# SPI_IO.net
KiCad netlist of a schematic drawn in Altium Designer
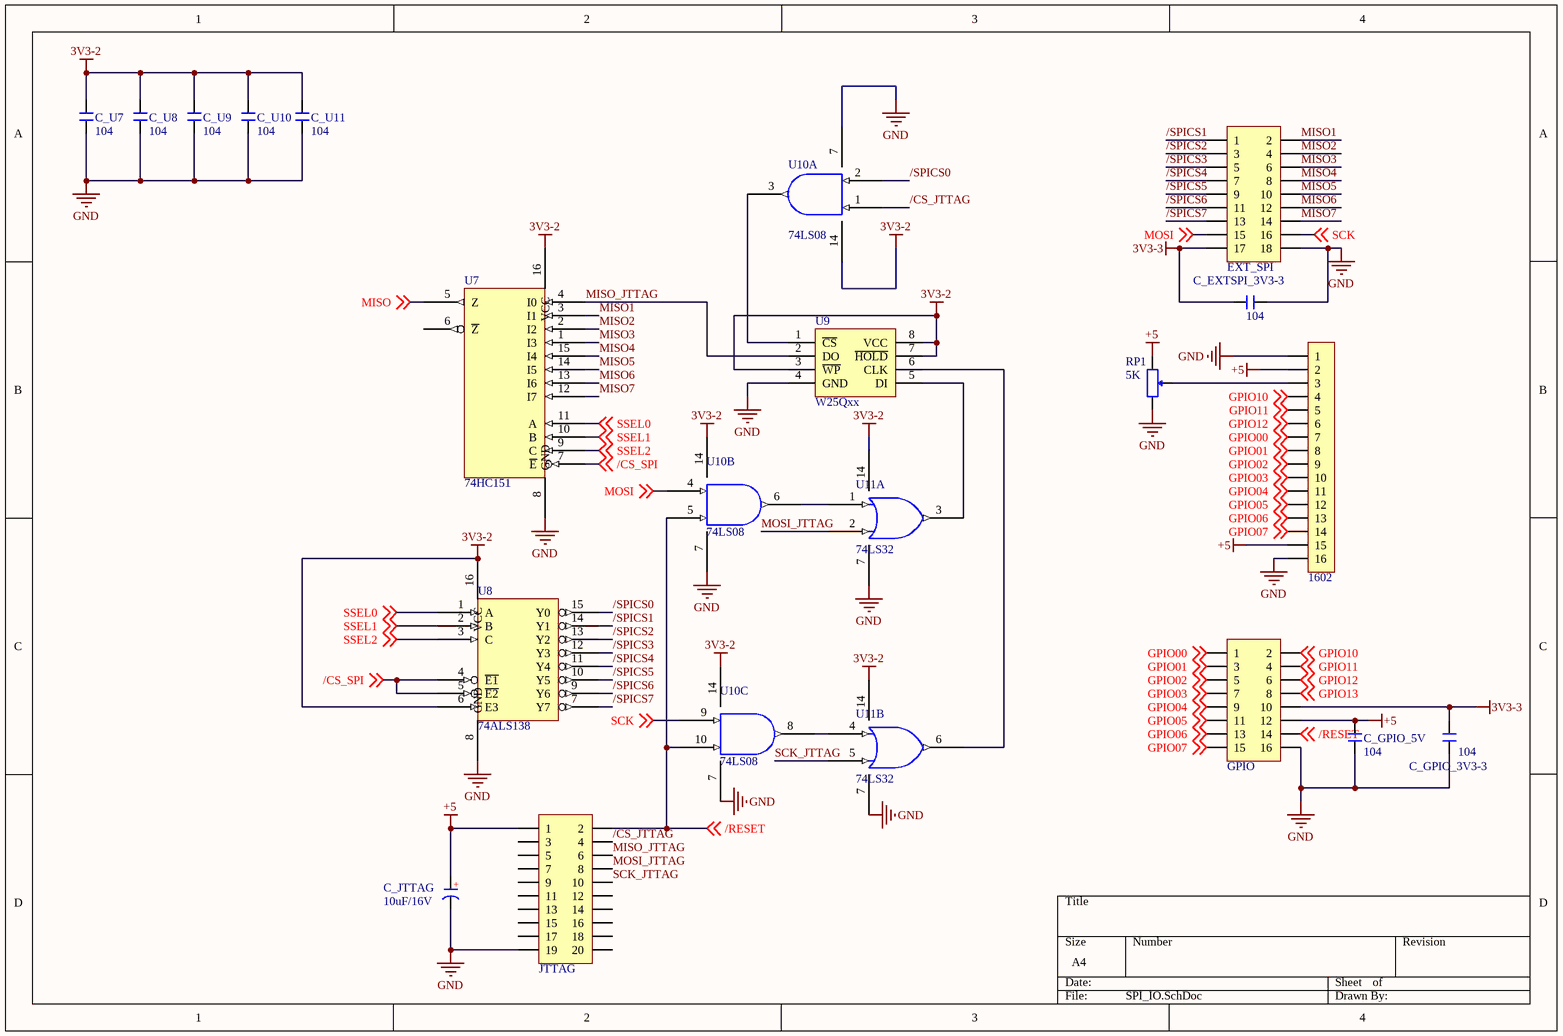
[diagram p0: SPI_IO.SchDoc]

(export (version "E")
  (design (tool "Eeschema 10.0.6"))
  (components
    (comp (ref "1602")
      (value "HDR-1X16")
      (footprint "SIP16")
      (description "16P接插件")
      (libsource (lib "4.5   - 接插件-脚距2.54") (part "Header 16"))
    )
    (comp (ref "C_EXTSPI_3V3-3")
      (value "104")
      (footprint "0805")
      (description "无极性贴片电容")
      (libsource (lib "3.1   - 电阻-电容-电感") (part "C"))
    )
    (comp (ref "C_GPIO_3V3-3")
      (value "104")
      (footprint "0805")
      (description "无极性贴片电容")
      (libsource (lib "3.1   - 电阻-电容-电感") (part "C"))
    )
    (comp (ref "C_GPIO_5V")
      (value "104")
      (footprint "0805")
      (description "无极性贴片电容")
      (libsource (lib "3.1   - 电阻-电容-电感") (part "C"))
    )
    (comp (ref "C_JTTAG")
      (value "10uF/16V")
      (footprint "RB.1/.2")
      (description "直插电解电容")
      (libsource (lib "3.1   - 电阻-电容-电感") (part "C-CAP"))
    )
    (comp (ref "C_U7")
      (value "104")
      (footprint "0805")
      (description "无极性贴片电容")
      (libsource (lib "3.1   - 电阻-电容-电感") (part "C"))
    )
    (comp (ref "C_U8")
      (value "104")
      (footprint "0805")
      (description "无极性贴片电容")
      (libsource (lib "3.1   - 电阻-电容-电感") (part "C"))
    )
    (comp (ref "C_U9")
      (value "104")
      (footprint "0805")
      (description "无极性贴片电容")
      (libsource (lib "3.1   - 电阻-电容-电感") (part "C"))
    )
    (comp (ref "C_U10")
      (value "104")
      (footprint "0805")
      (description "无极性贴片电容")
      (libsource (lib "3.1   - 电阻-电容-电感") (part "C"))
    )
    (comp (ref "C_U11")
      (value "104")
      (footprint "0805")
      (description "无极性贴片电容")
      (libsource (lib "3.1   - 电阻-电容-电感") (part "C"))
    )
    (comp (ref "EXT_SPI")
      (value "Header 9X2")
      (footprint "HDR2X9")
      (description "9*2P接插件")
      (libsource (lib "4.5   - 接插件-脚距2.54") (part "Header 9X2"))
    )
    (comp (ref "GPIO")
      (value "Header 8X2")
      (footprint "HDR2X8")
      (description "8*2P接插件")
      (libsource (lib "4.5   - 接插件-脚距2.54") (part "Header 8X2"))
    )
    (comp (ref "JTTAG")
      (value "Header 2X10")
      (footprint "IDC2.54-V20D")
      (description "10*2P接插件")
      (libsource (lib "4.5   - 接插件-脚距2.54") (part "Header 10X2"))
    )
    (comp (ref "RP1")
      (value "5K")
      (footprint "3303W")
      (description "贴片电位器")
      (libsource (lib "3.1   - 电阻-电容-电感") (part "RP-SMD"))
    )
    (comp (ref "U7") (value "74HC151") (footprint "SO-16") (libsource (lib "TTL74系列IC") (part "74HC151")))
    (comp (ref "U8") (value "74ALS138") (footprint "SO-16") (libsource (lib "TTL74系列IC") (part "74ALS138")))
    (comp (ref "U9")
      (value "W25Qxx")
      (footprint "SOIC-8")
      (description "外置Flash")
      (libsource (lib "1.1   - IC芯片") (part "W25Qxx"))
    )
    (comp (ref "U10") (value "74LS08") (footprint "SO-14") (libsource (lib "TTL74系列IC") (part "74LS08")))
    (comp (ref "U11") (value "74LS32") (footprint "SO-14") (libsource (lib "TTL74系列IC") (part "74LS32")))
  )
  (nets
    (net (code "1") (name "+5") (class "Default")
      (node (ref "1602") (pin "15") (pinfunction "15_15") (pintype "passive"))
      (node (ref "1602") (pin "2") (pinfunction "2_2") (pintype "passive"))
      (node (ref "C_GPIO_5V") (pin "2") (pinfunction "2_2") (pintype "passive"))
      (node (ref "C_JTTAG") (pin "1") (pinfunction "A_1") (pintype "passive"))
      (node (ref "GPIO") (pin "12") (pinfunction "12_12") (pintype "passive"))
      (node (ref "JTTAG") (pin "1") (pinfunction "1_1") (pintype "passive"))
      (node (ref "RP1") (pin "1") (pinfunction "1_1") (pintype "passive"))
    )
    (net (code "2") (name "/MISO1") (class "Default")
      (node (ref "EXT_SPI") (pin "2") (pinfunction "2_2") (pintype "passive"))
      (node (ref "U7") (pin "3") (pinfunction "I1_3") (pintype "input"))
    )
    (net (code "3") (name "/MISO2") (class "Default")
      (node (ref "EXT_SPI") (pin "4") (pinfunction "4_4") (pintype "passive"))
      (node (ref "U7") (pin "2") (pinfunction "I2_2") (pintype "input"))
    )
    (net (code "4") (name "/MISO3") (class "Default")
      (node (ref "EXT_SPI") (pin "6") (pinfunction "6_6") (pintype "passive"))
      (node (ref "U7") (pin "1") (pinfunction "I3_1") (pintype "input"))
    )
    (net (code "5") (name "/MISO4") (class "Default")
      (node (ref "EXT_SPI") (pin "8") (pinfunction "8_8") (pintype "passive"))
      (node (ref "U7") (pin "15") (pinfunction "I4_15") (pintype "input"))
    )
    (net (code "6") (name "/MISO5") (class "Default")
      (node (ref "EXT_SPI") (pin "10") (pinfunction "10_10") (pintype "passive"))
      (node (ref "U7") (pin "14") (pinfunction "I5_14") (pintype "input"))
    )
    (net (code "7") (name "/MISO6") (class "Default")
      (node (ref "EXT_SPI") (pin "12") (pinfunction "12_12") (pintype "passive"))
      (node (ref "U7") (pin "13") (pinfunction "I6_13") (pintype "input"))
    )
    (net (code "8") (name "/MISO7") (class "Default")
      (node (ref "EXT_SPI") (pin "14") (pinfunction "14_14") (pintype "passive"))
      (node (ref "U7") (pin "12") (pinfunction "I7_12") (pintype "input"))
    )
    (net (code "9") (name "/MISO_JTTAG") (class "Default")
      (node (ref "JTTAG") (pin "6") (pinfunction "6_6") (pintype "passive"))
      (node (ref "U7") (pin "4") (pinfunction "I0_4") (pintype "input"))
      (node (ref "U9") (pin "2") (pinfunction "DO_2") (pintype "passive"))
    )
    (net (code "10") (name "/MOSI_JTTAG") (class "Default")
      (node (ref "JTTAG") (pin "8") (pinfunction "8_8") (pintype "passive"))
      (node (ref "U11") (pin "2") (pintype "input"))
    )
    (net (code "11") (name "/SCK_JTTAG") (class "Default")
      (node (ref "JTTAG") (pin "10") (pinfunction "10_10") (pintype "passive"))
      (node (ref "U11") (pin "5") (pintype "input"))
    )
    (net (code "12") (name "/{slash}CS_JTTAG") (class "Default")
      (node (ref "JTTAG") (pin "4") (pinfunction "4_4") (pintype "passive"))
      (node (ref "U10") (pin "1") (pintype "input"))
    )
    (net (code "13") (name "/{slash}SPICS0") (class "Default")
      (node (ref "U10") (pin "2") (pintype "input"))
      (node (ref "U8") (pin "15") (pinfunction "Y0_15") (pintype "output"))
    )
    (net (code "14") (name "/{slash}SPICS1") (class "Default")
      (node (ref "EXT_SPI") (pin "1") (pinfunction "1_1") (pintype "passive"))
      (node (ref "U8") (pin "14") (pinfunction "Y1_14") (pintype "output"))
    )
    (net (code "15") (name "/{slash}SPICS2") (class "Default")
      (node (ref "EXT_SPI") (pin "3") (pinfunction "3_3") (pintype "passive"))
      (node (ref "U8") (pin "13") (pinfunction "Y2_13") (pintype "output"))
    )
    (net (code "16") (name "/{slash}SPICS3") (class "Default")
      (node (ref "EXT_SPI") (pin "5") (pinfunction "5_5") (pintype "passive"))
      (node (ref "U8") (pin "12") (pinfunction "Y3_12") (pintype "output"))
    )
    (net (code "17") (name "/{slash}SPICS4") (class "Default")
      (node (ref "EXT_SPI") (pin "7") (pinfunction "7_7") (pintype "passive"))
      (node (ref "U8") (pin "11") (pinfunction "Y4_11") (pintype "output"))
    )
    (net (code "18") (name "/{slash}SPICS5") (class "Default")
      (node (ref "EXT_SPI") (pin "9") (pinfunction "9_9") (pintype "passive"))
      (node (ref "U8") (pin "10") (pinfunction "Y5_10") (pintype "output"))
    )
    (net (code "19") (name "/{slash}SPICS6") (class "Default")
      (node (ref "EXT_SPI") (pin "11") (pinfunction "11_11") (pintype "passive"))
      (node (ref "U8") (pin "9") (pinfunction "Y6_9") (pintype "output"))
    )
    (net (code "20") (name "/{slash}SPICS7") (class "Default")
      (node (ref "EXT_SPI") (pin "13") (pinfunction "13_13") (pintype "passive"))
      (node (ref "U8") (pin "7") (pinfunction "Y7_7") (pintype "output"))
    )
    (net (code "21") (name "3V3-2") (class "Default")
      (node (ref "C_U10") (pin "2") (pinfunction "2_2") (pintype "passive"))
      (node (ref "C_U11") (pin "2") (pinfunction "2_2") (pintype "passive"))
      (node (ref "C_U7") (pin "2") (pinfunction "2_2") (pintype "passive"))
      (node (ref "C_U8") (pin "2") (pinfunction "2_2") (pintype "passive"))
      (node (ref "C_U9") (pin "2") (pinfunction "2_2") (pintype "passive"))
      (node (ref "U10") (pin "14") (pinfunction "VCC_14") (pintype "power_in"))
      (node (ref "U11") (pin "14") (pinfunction "VCC_14") (pintype "power_in"))
      (node (ref "U7") (pin "16") (pinfunction "VCC_16") (pintype "power_in"))
      (node (ref "U8") (pin "16") (pinfunction "VCC_16") (pintype "power_in"))
      (node (ref "U8") (pin "6") (pinfunction "E3_6") (pintype "input"))
      (node (ref "U9") (pin "3") (pinfunction "~{WP}_3") (pintype "passive"))
      (node (ref "U9") (pin "7") (pinfunction "~{HOLD}_7") (pintype "passive"))
      (node (ref "U9") (pin "8") (pinfunction "VCC_8") (pintype "passive"))
    )
    (net (code "22") (name "3V3-3") (class "Default")
      (node (ref "C_EXTSPI_3V3-3") (pin "1") (pinfunction "1_1") (pintype "passive"))
      (node (ref "C_GPIO_3V3-3") (pin "2") (pinfunction "2_2") (pintype "passive"))
      (node (ref "EXT_SPI") (pin "17") (pinfunction "17_17") (pintype "passive"))
      (node (ref "GPIO") (pin "10") (pinfunction "10_10") (pintype "passive"))
    )
    (net (code "23") (name "GND") (class "Default")
      (node (ref "1602") (pin "1") (pinfunction "1_1") (pintype "passive"))
      (node (ref "1602") (pin "16") (pinfunction "16_16") (pintype "passive"))
      (node (ref "C_EXTSPI_3V3-3") (pin "2") (pinfunction "2_2") (pintype "passive"))
      (node (ref "C_GPIO_3V3-3") (pin "1") (pinfunction "1_1") (pintype "passive"))
      (node (ref "C_GPIO_5V") (pin "1") (pinfunction "1_1") (pintype "passive"))
      (node (ref "C_JTTAG") (pin "2") (pinfunction "K_2") (pintype "passive"))
      (node (ref "C_U10") (pin "1") (pinfunction "1_1") (pintype "passive"))
      (node (ref "C_U11") (pin "1") (pinfunction "1_1") (pintype "passive"))
      (node (ref "C_U7") (pin "1") (pinfunction "1_1") (pintype "passive"))
      (node (ref "C_U8") (pin "1") (pinfunction "1_1") (pintype "passive"))
      (node (ref "C_U9") (pin "1") (pinfunction "1_1") (pintype "passive"))
      (node (ref "EXT_SPI") (pin "18") (pinfunction "18_18") (pintype "passive"))
      (node (ref "GPIO") (pin "16") (pinfunction "16_16") (pintype "passive"))
      (node (ref "JTTAG") (pin "19") (pinfunction "19_19") (pintype "passive"))
      (node (ref "RP1") (pin "3") (pinfunction "3_3") (pintype "passive"))
      (node (ref "U10") (pin "7") (pinfunction "GND_7") (pintype "power_in"))
      (node (ref "U11") (pin "7") (pinfunction "GND_7") (pintype "power_in"))
      (node (ref "U7") (pin "8") (pinfunction "GND_8") (pintype "power_in"))
      (node (ref "U8") (pin "8") (pinfunction "GND_8") (pintype "power_in"))
      (node (ref "U9") (pin "4") (pinfunction "GND_4") (pintype "passive"))
    )
    (net (code "24") (name "GPIO00") (class "Default")
      (node (ref "1602") (pin "7") (pinfunction "7_7") (pintype "passive"))
      (node (ref "GPIO") (pin "1") (pinfunction "1_1") (pintype "passive"))
    )
    (net (code "25") (name "GPIO01") (class "Default")
      (node (ref "1602") (pin "8") (pinfunction "8_8") (pintype "passive"))
      (node (ref "GPIO") (pin "3") (pinfunction "3_3") (pintype "passive"))
    )
    (net (code "26") (name "GPIO02") (class "Default")
      (node (ref "1602") (pin "9") (pinfunction "9_9") (pintype "passive"))
      (node (ref "GPIO") (pin "5") (pinfunction "5_5") (pintype "passive"))
    )
    (net (code "27") (name "GPIO03") (class "Default")
      (node (ref "1602") (pin "10") (pinfunction "10_10") (pintype "passive"))
      (node (ref "GPIO") (pin "7") (pinfunction "7_7") (pintype "passive"))
    )
    (net (code "28") (name "GPIO04") (class "Default")
      (node (ref "1602") (pin "11") (pinfunction "11_11") (pintype "passive"))
      (node (ref "GPIO") (pin "9") (pinfunction "9_9") (pintype "passive"))
    )
    (net (code "29") (name "GPIO05") (class "Default")
      (node (ref "1602") (pin "12") (pinfunction "12_12") (pintype "passive"))
      (node (ref "GPIO") (pin "11") (pinfunction "11_11") (pintype "passive"))
    )
    (net (code "30") (name "GPIO06") (class "Default")
      (node (ref "1602") (pin "13") (pinfunction "13_13") (pintype "passive"))
      (node (ref "GPIO") (pin "13") (pinfunction "13_13") (pintype "passive"))
    )
    (net (code "31") (name "GPIO07") (class "Default")
      (node (ref "1602") (pin "14") (pinfunction "14_14") (pintype "passive"))
      (node (ref "GPIO") (pin "15") (pinfunction "15_15") (pintype "passive"))
    )
    (net (code "32") (name "GPIO10") (class "Default")
      (node (ref "1602") (pin "4") (pinfunction "4_4") (pintype "passive"))
      (node (ref "GPIO") (pin "2") (pinfunction "2_2") (pintype "passive"))
    )
    (net (code "33") (name "GPIO11") (class "Default")
      (node (ref "1602") (pin "5") (pinfunction "5_5") (pintype "passive"))
      (node (ref "GPIO") (pin "4") (pinfunction "4_4") (pintype "passive"))
    )
    (net (code "34") (name "GPIO12") (class "Default")
      (node (ref "1602") (pin "6") (pinfunction "6_6") (pintype "passive"))
      (node (ref "GPIO") (pin "6") (pinfunction "6_6") (pintype "passive"))
    )
    (net (code "35") (name "GPIO13") (class "Default")
      (node (ref "GPIO") (pin "8") (pinfunction "8_8") (pintype "passive"))
    )
    (net (code "36") (name "MISO") (class "Default")
      (node (ref "U7") (pin "5") (pinfunction "Z_5") (pintype "output"))
    )
    (net (code "37") (name "MOSI") (class "Default")
      (node (ref "EXT_SPI") (pin "15") (pinfunction "15_15") (pintype "passive"))
      (node (ref "U10") (pin "4") (pintype "input"))
    )
    (net (code "38") (name "Net-(1602-Pad3)") (class "Default")
      (node (ref "1602") (pin "3") (pinfunction "3_3") (pintype "passive"))
      (node (ref "RP1") (pin "2") (pinfunction "2_2") (pintype "passive"))
    )
    (net (code "39") (name "Net-(U9-CLK)") (class "Default")
      (node (ref "U11") (pin "6") (pintype "output"))
      (node (ref "U9") (pin "6") (pinfunction "CLK_6") (pintype "passive"))
    )
    (net (code "40") (name "Net-(U9-DI)") (class "Default")
      (node (ref "U11") (pin "3") (pintype "output"))
      (node (ref "U9") (pin "5") (pinfunction "DI_5") (pintype "passive"))
    )
    (net (code "41") (name "Net-(U9-~{CS})") (class "Default")
      (node (ref "U10") (pin "3") (pintype "output"))
      (node (ref "U9") (pin "1") (pinfunction "~{CS}_1") (pintype "passive"))
    )
    (net (code "42") (name "Net-(U10-Pad6)") (class "Default")
      (node (ref "U10") (pin "6") (pintype "output"))
      (node (ref "U11") (pin "1") (pintype "input"))
    )
    (net (code "43") (name "Net-(U10-Pad8)") (class "Default")
      (node (ref "U10") (pin "8") (pintype "output"))
      (node (ref "U11") (pin "4") (pintype "input"))
    )
    (net (code "44") (name "SCK") (class "Default")
      (node (ref "EXT_SPI") (pin "16") (pinfunction "16_16") (pintype "passive"))
      (node (ref "U10") (pin "9") (pintype "input"))
    )
    (net (code "45") (name "SSEL0") (class "Default")
      (node (ref "U7") (pin "11") (pinfunction "A_11") (pintype "input"))
      (node (ref "U8") (pin "1") (pinfunction "A_1") (pintype "input"))
    )
    (net (code "46") (name "SSEL1") (class "Default")
      (node (ref "U7") (pin "10") (pinfunction "B_10") (pintype "input"))
      (node (ref "U8") (pin "2") (pinfunction "B_2") (pintype "input"))
    )
    (net (code "47") (name "SSEL2") (class "Default")
      (node (ref "U7") (pin "9") (pinfunction "C_9") (pintype "input"))
      (node (ref "U8") (pin "3") (pinfunction "C_3") (pintype "input"))
    )
    (net (code "48") (name "unconnected-(JTTAG-Pad3)") (class "Default")
      (node (ref "JTTAG") (pin "3") (pinfunction "3_3") (pintype "passive"))
    )
    (net (code "49") (name "unconnected-(JTTAG-Pad5)") (class "Default")
      (node (ref "JTTAG") (pin "5") (pinfunction "5_5") (pintype "passive"))
    )
    (net (code "50") (name "unconnected-(JTTAG-Pad7)") (class "Default")
      (node (ref "JTTAG") (pin "7") (pinfunction "7_7") (pintype "passive"))
    )
    (net (code "51") (name "unconnected-(JTTAG-Pad9)") (class "Default")
      (node (ref "JTTAG") (pin "9") (pinfunction "9_9") (pintype "passive"))
    )
    (net (code "52") (name "unconnected-(JTTAG-Pad11)") (class "Default")
      (node (ref "JTTAG") (pin "11") (pinfunction "11_11") (pintype "passive"))
    )
    (net (code "53") (name "unconnected-(JTTAG-Pad12)") (class "Default")
      (node (ref "JTTAG") (pin "12") (pinfunction "12_12") (pintype "passive"))
    )
    (net (code "54") (name "unconnected-(JTTAG-Pad13)") (class "Default")
      (node (ref "JTTAG") (pin "13") (pinfunction "13_13") (pintype "passive"))
    )
    (net (code "55") (name "unconnected-(JTTAG-Pad14)") (class "Default")
      (node (ref "JTTAG") (pin "14") (pinfunction "14_14") (pintype "passive"))
    )
    (net (code "56") (name "unconnected-(JTTAG-Pad15)") (class "Default")
      (node (ref "JTTAG") (pin "15") (pinfunction "15_15") (pintype "passive"))
    )
    (net (code "57") (name "unconnected-(JTTAG-Pad16)") (class "Default")
      (node (ref "JTTAG") (pin "16") (pinfunction "16_16") (pintype "passive"))
    )
    (net (code "58") (name "unconnected-(JTTAG-Pad17)") (class "Default")
      (node (ref "JTTAG") (pin "17") (pinfunction "17_17") (pintype "passive"))
    )
    (net (code "59") (name "unconnected-(JTTAG-Pad18)") (class "Default")
      (node (ref "JTTAG") (pin "18") (pinfunction "18_18") (pintype "passive"))
    )
    (net (code "60") (name "unconnected-(JTTAG-Pad20)") (class "Default")
      (node (ref "JTTAG") (pin "20") (pinfunction "20_20") (pintype "passive"))
    )
    (net (code "61") (name "unconnected-(U7-~{Z}-Pad6)") (class "Default")
      (node (ref "U7") (pin "6") (pinfunction "~{Z}_6") (pintype "output"))
    )
    (net (code "62") (name "{slash}CS_SPI") (class "Default")
      (node (ref "U7") (pin "7") (pinfunction "~{E}_7") (pintype "input"))
      (node (ref "U8") (pin "4") (pinfunction "~{E1}_4") (pintype "input"))
      (node (ref "U8") (pin "5") (pinfunction "~{E2}_5") (pintype "input"))
    )
    (net (code "63") (name "{slash}RESET") (class "Default")
      (node (ref "GPIO") (pin "14") (pinfunction "14_14") (pintype "passive"))
      (node (ref "JTTAG") (pin "2") (pinfunction "2_2") (pintype "passive"))
      (node (ref "U10") (pin "10") (pintype "input"))
      (node (ref "U10") (pin "5") (pintype "input"))
    )
  )
)
